# accelerometer.net
KiCad netlist of a schematic drawn in Altium Designer
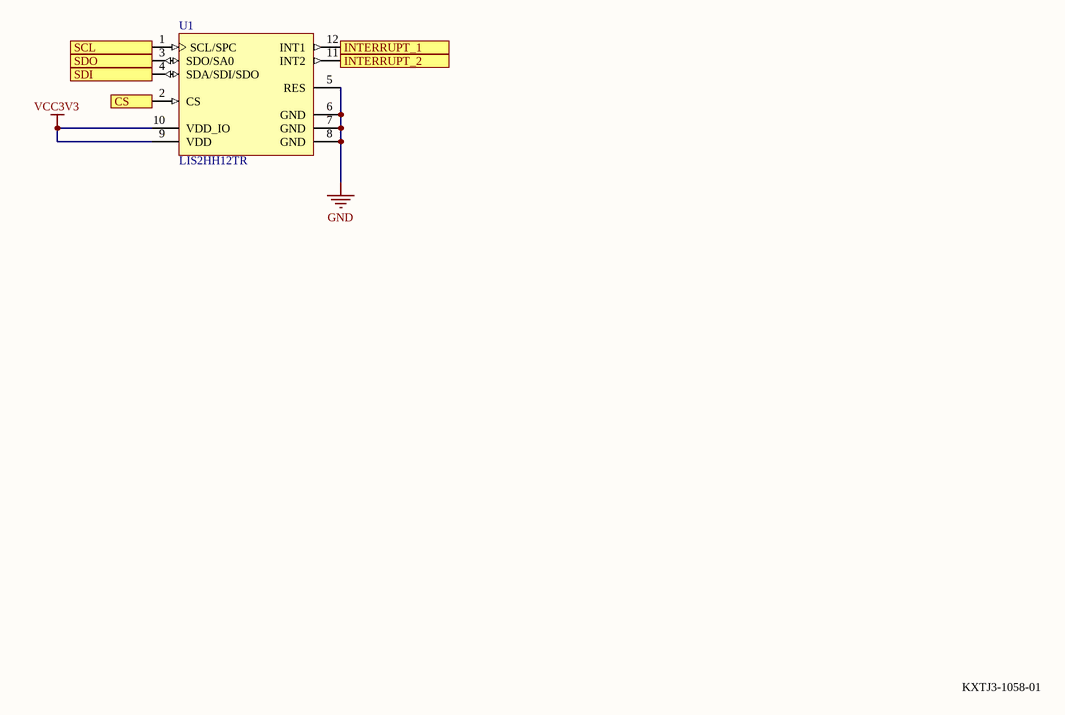
[diagram p0: accelerometer.SchDoc]

(export (version "E")
  (design (tool "Eeschema 10.0.6"))
  (components
    (comp (ref "U1")
      (value "LIS2HH12TR")
      (footprint "STM-LGA-12")
      (fields (field (name "MANUFACTURER") "STMicroelectronics"))
      (libsource (lib "Altium Content Vault") (part "STM-LIS2HH12-LGA-12"))
    )
  )
  (nets
    (net (code "1") (name "/CS") (class "Default")
      (node (ref "U1") (pin "2") (pinfunction "CS_2") (pintype "input"))
    )
    (net (code "2") (name "/INTERRUPT_1") (class "Default")
      (node (ref "U1") (pin "12") (pinfunction "INT1_12") (pintype "output"))
    )
    (net (code "3") (name "/INTERRUPT_2") (class "Default")
      (node (ref "U1") (pin "11") (pinfunction "INT2_11") (pintype "output"))
    )
    (net (code "4") (name "/SCL") (class "Default")
      (node (ref "U1") (pin "1") (pinfunction "SCL/SPC_1") (pintype "input"))
    )
    (net (code "5") (name "/SDI") (class "Default")
      (node (ref "U1") (pin "4") (pinfunction "SDA/SDI/SDO_4") (pintype "bidirectional"))
    )
    (net (code "6") (name "/SDO") (class "Default")
      (node (ref "U1") (pin "3") (pinfunction "SDO/SA0_3") (pintype "bidirectional"))
    )
    (net (code "7") (name "GND") (class "Default")
      (node (ref "U1") (pin "5") (pinfunction "RES_5") (pintype "passive"))
      (node (ref "U1") (pin "6") (pinfunction "GND_6") (pintype "power_in"))
      (node (ref "U1") (pin "7") (pinfunction "GND_7") (pintype "power_in"))
      (node (ref "U1") (pin "8") (pinfunction "GND_8") (pintype "power_in"))
    )
    (net (code "8") (name "VCC3V3") (class "Default")
      (node (ref "U1") (pin "10") (pinfunction "VDD_IO_10") (pintype "power_in"))
      (node (ref "U1") (pin "9") (pinfunction "VDD_9") (pintype "power_in"))
    )
  )
)
